# Sensors.net
KiCad netlist of a schematic drawn in Altium Designer
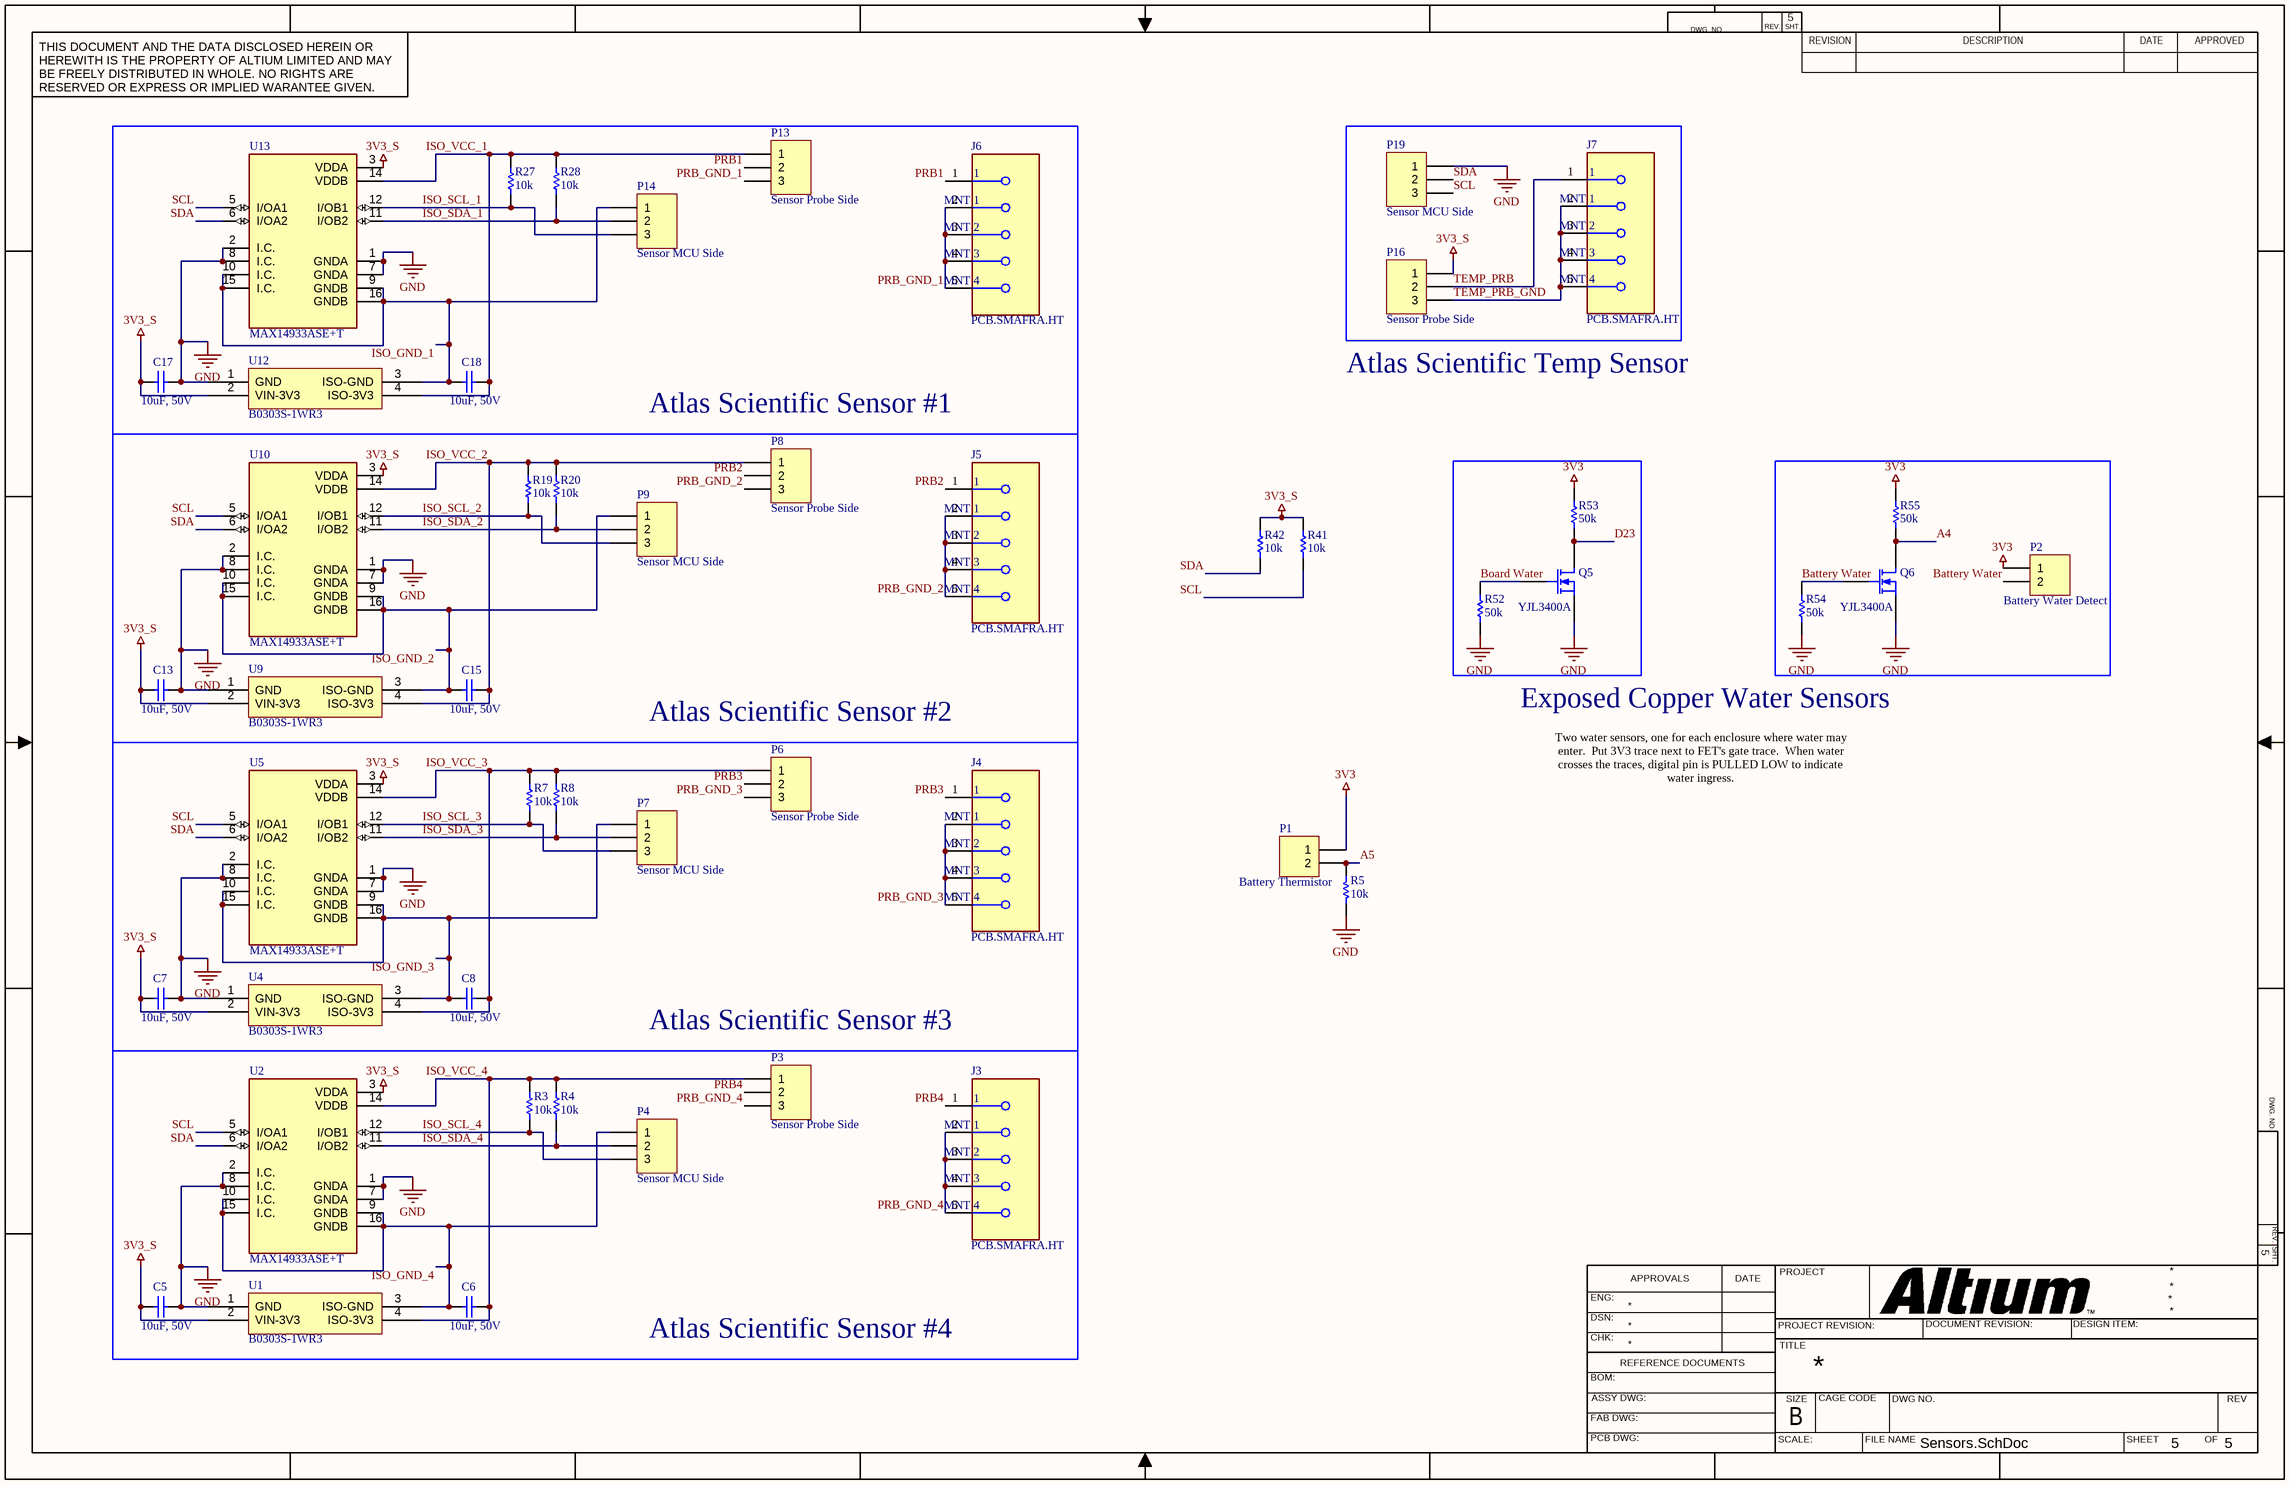
[diagram p0: Sensors.SchDoc]

(export (version "E")
  (design (tool "Eeschema 10.0.6"))
  (components
    (comp (ref "C5")
      (value "10uF, 50V")
      (footprint "CAPC2012X145N")
      (description "Capacitor")
      (libsource (lib "Simulation Generic Components") (part "Capacitor"))
    )
    (comp (ref "C6")
      (value "10uF, 50V")
      (footprint "CAPC2012X145N")
      (description "Capacitor")
      (libsource (lib "Simulation Generic Components") (part "Capacitor"))
    )
    (comp (ref "C7")
      (value "10uF, 50V")
      (footprint "CAPC2012X145N")
      (description "Capacitor")
      (libsource (lib "Simulation Generic Components") (part "Capacitor"))
    )
    (comp (ref "C8")
      (value "10uF, 50V")
      (footprint "CAPC2012X145N")
      (description "Capacitor")
      (libsource (lib "Simulation Generic Components") (part "Capacitor"))
    )
    (comp (ref "C13")
      (value "10uF, 50V")
      (footprint "CAPC2012X145N")
      (description "Capacitor")
      (libsource (lib "Simulation Generic Components") (part "Capacitor"))
    )
    (comp (ref "C15")
      (value "10uF, 50V")
      (footprint "CAPC2012X145N")
      (description "Capacitor")
      (libsource (lib "Simulation Generic Components") (part "Capacitor"))
    )
    (comp (ref "C17")
      (value "10uF, 50V")
      (footprint "CAPC2012X145N")
      (description "Capacitor")
      (libsource (lib "Simulation Generic Components") (part "Capacitor"))
    )
    (comp (ref "C18")
      (value "10uF, 50V")
      (footprint "CAPC2012X145N")
      (description "Capacitor")
      (libsource (lib "Simulation Generic Components") (part "Capacitor"))
    )
    (comp (ref "J3")
      (value "PCB.SMAFRA.HT")
      (footprint "FP-PCB_SMAFRA_HT-MFG")
      (description "CONN SMA JACK R/A 50OHM PCB")
      (libsource (lib "Altium Content Vault") (part "9c40ac4d87bbbe9fcb330bd20f98ca3"))
    )
    (comp (ref "J4")
      (value "PCB.SMAFRA.HT")
      (footprint "FP-PCB_SMAFRA_HT-MFG")
      (description "CONN SMA JACK R/A 50OHM PCB")
      (libsource (lib "Altium Content Vault") (part "9c40ac4d87bbbe9fcb330bd20f98ca3"))
    )
    (comp (ref "J5")
      (value "PCB.SMAFRA.HT")
      (footprint "FP-PCB_SMAFRA_HT-MFG")
      (description "CONN SMA JACK R/A 50OHM PCB")
      (libsource (lib "Altium Content Vault") (part "9c40ac4d87bbbe9fcb330bd20f98ca3"))
    )
    (comp (ref "J6")
      (value "PCB.SMAFRA.HT")
      (footprint "FP-PCB_SMAFRA_HT-MFG")
      (description "CONN SMA JACK R/A 50OHM PCB")
      (libsource (lib "Altium Content Vault") (part "9c40ac4d87bbbe9fcb330bd20f98ca3"))
    )
    (comp (ref "J7")
      (value "PCB.SMAFRA.HT")
      (footprint "FP-PCB_SMAFRA_HT-MFG")
      (description "CONN SMA JACK R/A 50OHM PCB")
      (libsource (lib "Altium Content Vault") (part "9c40ac4d87bbbe9fcb330bd20f98ca3"))
    )
    (comp (ref "P1")
      (value "Battery Thermistor")
      (footprint "TE_6-440054-2")
      (description "Header, 2-Pin")
      (fields (field (name "PUBLISHER") "Altium Limited"))
      (libsource (lib "") (part "Header 2_1"))
    )
    (comp (ref "P2")
      (value "Battery Water Detect")
      (footprint "TE_6-440054-2")
      (description "Header, 2-Pin")
      (fields (field (name "PUBLISHER") "Altium Limited"))
      (libsource (lib "Miscellaneous Connectors") (part "Header 2"))
    )
    (comp (ref "P3")
      (value "Sensor Probe Side")
      (footprint "1x3 Header")
      (description "Header, 3-Pin")
      (fields (field (name "PUBLISHER") "Altium Limited"))
      (libsource (lib "Miscellaneous Connectors") (part "Header 3"))
    )
    (comp (ref "P4")
      (value "Sensor MCU Side")
      (footprint "1x3 Header")
      (description "Header, 3-Pin")
      (fields (field (name "PUBLISHER") "Altium Limited"))
      (libsource (lib "Miscellaneous Connectors") (part "Header 3"))
    )
    (comp (ref "P6")
      (value "Sensor Probe Side")
      (footprint "1x3 Header")
      (description "Header, 3-Pin")
      (fields (field (name "PUBLISHER") "Altium Limited"))
      (libsource (lib "Miscellaneous Connectors") (part "Header 3"))
    )
    (comp (ref "P7")
      (value "Sensor MCU Side")
      (footprint "1x3 Header")
      (description "Header, 3-Pin")
      (fields (field (name "PUBLISHER") "Altium Limited"))
      (libsource (lib "Miscellaneous Connectors") (part "Header 3"))
    )
    (comp (ref "P8")
      (value "Sensor Probe Side")
      (footprint "1x3 Header")
      (description "Header, 3-Pin")
      (fields (field (name "PUBLISHER") "Altium Limited"))
      (libsource (lib "Miscellaneous Connectors") (part "Header 3"))
    )
    (comp (ref "P9")
      (value "Sensor MCU Side")
      (footprint "1x3 Header")
      (description "Header, 3-Pin")
      (fields (field (name "PUBLISHER") "Altium Limited"))
      (libsource (lib "Miscellaneous Connectors") (part "Header 3"))
    )
    (comp (ref "P13")
      (value "Sensor Probe Side")
      (footprint "1x3 Header")
      (description "Header, 3-Pin")
      (fields (field (name "PUBLISHER") "Altium Limited"))
      (libsource (lib "Miscellaneous Connectors") (part "Header 3"))
    )
    (comp (ref "P14")
      (value "Sensor MCU Side")
      (footprint "1x3 Header")
      (description "Header, 3-Pin")
      (fields (field (name "PUBLISHER") "Altium Limited"))
      (libsource (lib "Miscellaneous Connectors") (part "Header 3"))
    )
    (comp (ref "P16")
      (value "Sensor Probe Side")
      (footprint "1x3 Header")
      (description "Header, 3-Pin")
      (fields (field (name "PUBLISHER") "Altium Limited"))
      (libsource (lib "") (part "Header 3_2"))
    )
    (comp (ref "P19")
      (value "Sensor MCU Side")
      (footprint "1x3 Header")
      (description "Header, 3-Pin")
      (fields (field (name "PUBLISHER") "Altium Limited"))
      (libsource (lib "") (part "Header 3_1"))
    )
    (comp (ref "Q5")
      (value "YJL3400A")
      (footprint "SOT23-3")
      (description "N-Channel MOSFET")
      (fields (field (name "PUBLISHER") "Altium Limited"))
      (libsource (lib "Miscellaneous Devices") (part "MOSFET-N"))
    )
    (comp (ref "Q6")
      (value "YJL3400A")
      (footprint "SOT23-3")
      (description "N-Channel MOSFET")
      (fields (field (name "PUBLISHER") "Altium Limited"))
      (libsource (lib "Miscellaneous Devices") (part "MOSFET-N"))
    )
    (comp (ref "R3")
      (value "10k")
      (footprint "0603 Resistor")
      (description "Resistor")
      (libsource (lib "Simulation Generic Components") (part "Resistor"))
    )
    (comp (ref "R4")
      (value "10k")
      (footprint "0603 Resistor")
      (description "Resistor")
      (libsource (lib "Simulation Generic Components") (part "Resistor"))
    )
    (comp (ref "R5")
      (value "10k")
      (footprint "0603 Resistor")
      (description "Resistor")
      (libsource (lib "Simulation Generic Components") (part "Resistor"))
    )
    (comp (ref "R7")
      (value "10k")
      (footprint "0603 Resistor")
      (description "Resistor")
      (libsource (lib "Simulation Generic Components") (part "Resistor"))
    )
    (comp (ref "R8")
      (value "10k")
      (footprint "0603 Resistor")
      (description "Resistor")
      (libsource (lib "Simulation Generic Components") (part "Resistor"))
    )
    (comp (ref "R19")
      (value "10k")
      (footprint "0603 Resistor")
      (description "Resistor")
      (libsource (lib "Simulation Generic Components") (part "Resistor"))
    )
    (comp (ref "R20")
      (value "10k")
      (footprint "0603 Resistor")
      (description "Resistor")
      (libsource (lib "Simulation Generic Components") (part "Resistor"))
    )
    (comp (ref "R27")
      (value "10k")
      (footprint "0603 Resistor")
      (description "Resistor")
      (libsource (lib "Simulation Generic Components") (part "Resistor"))
    )
    (comp (ref "R28")
      (value "10k")
      (footprint "0603 Resistor")
      (description "Resistor")
      (libsource (lib "Simulation Generic Components") (part "Resistor"))
    )
    (comp (ref "R41")
      (value "10k")
      (footprint "0603 Resistor")
      (description "Resistor")
      (libsource (lib "Simulation Generic Components") (part "Resistor"))
    )
    (comp (ref "R42")
      (value "10k")
      (footprint "0603 Resistor")
      (description "Resistor")
      (libsource (lib "Simulation Generic Components") (part "Resistor"))
    )
    (comp (ref "R52")
      (value "50k")
      (footprint "0603 Resistor")
      (description "Resistor")
      (libsource (lib "Simulation Generic Components") (part "Resistor"))
    )
    (comp (ref "R53")
      (value "50k")
      (footprint "0603 Resistor")
      (description "Resistor")
      (libsource (lib "Simulation Generic Components") (part "Resistor"))
    )
    (comp (ref "R54")
      (value "50k")
      (footprint "0603 Resistor")
      (description "Resistor")
      (libsource (lib "Simulation Generic Components") (part "Resistor"))
    )
    (comp (ref "R55")
      (value "50k")
      (footprint "0603 Resistor")
      (description "Resistor")
      (libsource (lib "Simulation Generic Components") (part "Resistor"))
    )
    (comp (ref "U1")
      (value "B0303S-1WR3")
      (footprint "B0303S-1WR3")
      (description "3V3 Isolator")
      (libsource (lib "WaterNet23BotPCB") (part "B0303S-1WR3"))
    )
    (comp (ref "U2")
      (value "MAX14933ASE+T")
      (footprint "SOIC127P600X175-16N")
      (libsource (lib "MAX14933ASE+T") (part "MAX14933ASE+T"))
    )
    (comp (ref "U4")
      (value "B0303S-1WR3")
      (footprint "B0303S-1WR3")
      (description "3V3 Isolator")
      (libsource (lib "WaterNet23BotPCB") (part "B0303S-1WR3"))
    )
    (comp (ref "U5")
      (value "MAX14933ASE+T")
      (footprint "SOIC127P600X175-16N")
      (libsource (lib "MAX14933ASE+T") (part "MAX14933ASE+T"))
    )
    (comp (ref "U9")
      (value "B0303S-1WR3")
      (footprint "B0303S-1WR3")
      (description "3V3 Isolator")
      (libsource (lib "WaterNet23BotPCB") (part "B0303S-1WR3"))
    )
    (comp (ref "U10")
      (value "MAX14933ASE+T")
      (footprint "SOIC127P600X175-16N")
      (libsource (lib "MAX14933ASE+T") (part "MAX14933ASE+T"))
    )
    (comp (ref "U12")
      (value "B0303S-1WR3")
      (footprint "B0303S-1WR3")
      (description "3V3 Isolator")
      (libsource (lib "WaterNet23BotPCB") (part "B0303S-1WR3"))
    )
    (comp (ref "U13")
      (value "MAX14933ASE+T")
      (footprint "SOIC127P600X175-16N")
      (libsource (lib "MAX14933ASE+T") (part "MAX14933ASE+T"))
    )
  )
  (nets
    (net (code "1") (name "/A4") (class "Default")
      (node (ref "Q6") (pin "3") (pinfunction "D_3") (pintype "passive"))
      (node (ref "R55") (pin "1") (pinfunction "1_1") (pintype "passive"))
    )
    (net (code "2") (name "/A5") (class "Default")
      (node (ref "P1") (pin "2") (pinfunction "2_2") (pintype "passive"))
      (node (ref "R5") (pin "2") (pinfunction "2_2") (pintype "passive"))
    )
    (net (code "3") (name "/Battery Water") (class "Default")
      (node (ref "P2") (pin "2") (pinfunction "2_2") (pintype "passive"))
      (node (ref "Q6") (pin "1") (pinfunction "G_1") (pintype "passive"))
      (node (ref "R54") (pin "2") (pinfunction "2_2") (pintype "passive"))
    )
    (net (code "4") (name "/Board Water") (class "Default")
      (node (ref "Q5") (pin "1") (pinfunction "G_1") (pintype "passive"))
      (node (ref "R52") (pin "2") (pinfunction "2_2") (pintype "passive"))
    )
    (net (code "5") (name "/D23") (class "Default")
      (node (ref "Q5") (pin "3") (pinfunction "D_3") (pintype "passive"))
      (node (ref "R53") (pin "1") (pinfunction "1_1") (pintype "passive"))
    )
    (net (code "6") (name "/ISO_GND_1") (class "Default")
      (node (ref "C18") (pin "1") (pinfunction "1_1") (pintype "passive"))
      (node (ref "P14") (pin "1") (pinfunction "1_1") (pintype "passive"))
      (node (ref "U12") (pin "3") (pinfunction "ISO-GND_3") (pintype "power_in"))
      (node (ref "U13") (pin "10") (pinfunction "I.C._10") (pintype "passive"))
      (node (ref "U13") (pin "15") (pinfunction "I.C._15") (pintype "passive"))
      (node (ref "U13") (pin "16") (pinfunction "GNDB_16") (pintype "power_in"))
      (node (ref "U13") (pin "9") (pinfunction "GNDB_9") (pintype "power_in"))
    )
    (net (code "7") (name "/ISO_GND_2") (class "Default")
      (node (ref "C15") (pin "1") (pinfunction "1_1") (pintype "passive"))
      (node (ref "P9") (pin "1") (pinfunction "1_1") (pintype "passive"))
      (node (ref "U10") (pin "10") (pinfunction "I.C._10") (pintype "passive"))
      (node (ref "U10") (pin "15") (pinfunction "I.C._15") (pintype "passive"))
      (node (ref "U10") (pin "16") (pinfunction "GNDB_16") (pintype "power_in"))
      (node (ref "U10") (pin "9") (pinfunction "GNDB_9") (pintype "power_in"))
      (node (ref "U9") (pin "3") (pinfunction "ISO-GND_3") (pintype "power_in"))
    )
    (net (code "8") (name "/ISO_GND_3") (class "Default")
      (node (ref "C8") (pin "1") (pinfunction "1_1") (pintype "passive"))
      (node (ref "P7") (pin "1") (pinfunction "1_1") (pintype "passive"))
      (node (ref "U4") (pin "3") (pinfunction "ISO-GND_3") (pintype "power_in"))
      (node (ref "U5") (pin "10") (pinfunction "I.C._10") (pintype "passive"))
      (node (ref "U5") (pin "15") (pinfunction "I.C._15") (pintype "passive"))
      (node (ref "U5") (pin "16") (pinfunction "GNDB_16") (pintype "power_in"))
      (node (ref "U5") (pin "9") (pinfunction "GNDB_9") (pintype "power_in"))
    )
    (net (code "9") (name "/ISO_GND_4") (class "Default")
      (node (ref "C6") (pin "1") (pinfunction "1_1") (pintype "passive"))
      (node (ref "P4") (pin "1") (pinfunction "1_1") (pintype "passive"))
      (node (ref "U1") (pin "3") (pinfunction "ISO-GND_3") (pintype "power_in"))
      (node (ref "U2") (pin "10") (pinfunction "I.C._10") (pintype "passive"))
      (node (ref "U2") (pin "15") (pinfunction "I.C._15") (pintype "passive"))
      (node (ref "U2") (pin "16") (pinfunction "GNDB_16") (pintype "power_in"))
      (node (ref "U2") (pin "9") (pinfunction "GNDB_9") (pintype "power_in"))
    )
    (net (code "10") (name "/ISO_SCL_1") (class "Default")
      (node (ref "P14") (pin "3") (pinfunction "3_3") (pintype "passive"))
      (node (ref "R27") (pin "1") (pinfunction "1_1") (pintype "passive"))
      (node (ref "U13") (pin "12") (pinfunction "I/OB1_12") (pintype "bidirectional"))
    )
    (net (code "11") (name "/ISO_SCL_2") (class "Default")
      (node (ref "P9") (pin "3") (pinfunction "3_3") (pintype "passive"))
      (node (ref "R19") (pin "1") (pinfunction "1_1") (pintype "passive"))
      (node (ref "U10") (pin "12") (pinfunction "I/OB1_12") (pintype "bidirectional"))
    )
    (net (code "12") (name "/ISO_SCL_3") (class "Default")
      (node (ref "P7") (pin "3") (pinfunction "3_3") (pintype "passive"))
      (node (ref "R7") (pin "1") (pinfunction "1_1") (pintype "passive"))
      (node (ref "U5") (pin "12") (pinfunction "I/OB1_12") (pintype "bidirectional"))
    )
    (net (code "13") (name "/ISO_SCL_4") (class "Default")
      (node (ref "P4") (pin "3") (pinfunction "3_3") (pintype "passive"))
      (node (ref "R3") (pin "1") (pinfunction "1_1") (pintype "passive"))
      (node (ref "U2") (pin "12") (pinfunction "I/OB1_12") (pintype "bidirectional"))
    )
    (net (code "14") (name "/ISO_SDA_1") (class "Default")
      (node (ref "P14") (pin "2") (pinfunction "2_2") (pintype "passive"))
      (node (ref "R28") (pin "1") (pinfunction "1_1") (pintype "passive"))
      (node (ref "U13") (pin "11") (pinfunction "I/OB2_11") (pintype "bidirectional"))
    )
    (net (code "15") (name "/ISO_SDA_2") (class "Default")
      (node (ref "P9") (pin "2") (pinfunction "2_2") (pintype "passive"))
      (node (ref "R20") (pin "1") (pinfunction "1_1") (pintype "passive"))
      (node (ref "U10") (pin "11") (pinfunction "I/OB2_11") (pintype "bidirectional"))
    )
    (net (code "16") (name "/ISO_SDA_3") (class "Default")
      (node (ref "P7") (pin "2") (pinfunction "2_2") (pintype "passive"))
      (node (ref "R8") (pin "1") (pinfunction "1_1") (pintype "passive"))
      (node (ref "U5") (pin "11") (pinfunction "I/OB2_11") (pintype "bidirectional"))
    )
    (net (code "17") (name "/ISO_SDA_4") (class "Default")
      (node (ref "P4") (pin "2") (pinfunction "2_2") (pintype "passive"))
      (node (ref "R4") (pin "1") (pinfunction "1_1") (pintype "passive"))
      (node (ref "U2") (pin "11") (pinfunction "I/OB2_11") (pintype "bidirectional"))
    )
    (net (code "18") (name "/ISO_VCC_1") (class "Default")
      (node (ref "C18") (pin "2") (pinfunction "2_2") (pintype "passive"))
      (node (ref "P13") (pin "1") (pinfunction "1_1") (pintype "passive"))
      (node (ref "R27") (pin "2") (pinfunction "2_2") (pintype "passive"))
      (node (ref "R28") (pin "2") (pinfunction "2_2") (pintype "passive"))
      (node (ref "U12") (pin "4") (pinfunction "ISO-3V3_4") (pintype "power_in"))
      (node (ref "U13") (pin "14") (pinfunction "VDDB_14") (pintype "power_in"))
    )
    (net (code "19") (name "/ISO_VCC_2") (class "Default")
      (node (ref "C15") (pin "2") (pinfunction "2_2") (pintype "passive"))
      (node (ref "P8") (pin "1") (pinfunction "1_1") (pintype "passive"))
      (node (ref "R19") (pin "2") (pinfunction "2_2") (pintype "passive"))
      (node (ref "R20") (pin "2") (pinfunction "2_2") (pintype "passive"))
      (node (ref "U10") (pin "14") (pinfunction "VDDB_14") (pintype "power_in"))
      (node (ref "U9") (pin "4") (pinfunction "ISO-3V3_4") (pintype "power_in"))
    )
    (net (code "20") (name "/ISO_VCC_3") (class "Default")
      (node (ref "C8") (pin "2") (pinfunction "2_2") (pintype "passive"))
      (node (ref "P6") (pin "1") (pinfunction "1_1") (pintype "passive"))
      (node (ref "R7") (pin "2") (pinfunction "2_2") (pintype "passive"))
      (node (ref "R8") (pin "2") (pinfunction "2_2") (pintype "passive"))
      (node (ref "U4") (pin "4") (pinfunction "ISO-3V3_4") (pintype "power_in"))
      (node (ref "U5") (pin "14") (pinfunction "VDDB_14") (pintype "power_in"))
    )
    (net (code "21") (name "/ISO_VCC_4") (class "Default")
      (node (ref "C6") (pin "2") (pinfunction "2_2") (pintype "passive"))
      (node (ref "P3") (pin "1") (pinfunction "1_1") (pintype "passive"))
      (node (ref "R3") (pin "2") (pinfunction "2_2") (pintype "passive"))
      (node (ref "R4") (pin "2") (pinfunction "2_2") (pintype "passive"))
      (node (ref "U1") (pin "4") (pinfunction "ISO-3V3_4") (pintype "power_in"))
      (node (ref "U2") (pin "14") (pinfunction "VDDB_14") (pintype "power_in"))
    )
    (net (code "22") (name "/PRB1") (class "Default")
      (node (ref "J6") (pin "1") (pinfunction "1_1") (pintype "passive"))
      (node (ref "P13") (pin "2") (pinfunction "2_2") (pintype "passive"))
    )
    (net (code "23") (name "/PRB2") (class "Default")
      (node (ref "J5") (pin "1") (pinfunction "1_1") (pintype "passive"))
      (node (ref "P8") (pin "2") (pinfunction "2_2") (pintype "passive"))
    )
    (net (code "24") (name "/PRB3") (class "Default")
      (node (ref "J4") (pin "1") (pinfunction "1_1") (pintype "passive"))
      (node (ref "P6") (pin "2") (pinfunction "2_2") (pintype "passive"))
    )
    (net (code "25") (name "/PRB4") (class "Default")
      (node (ref "J3") (pin "1") (pinfunction "1_1") (pintype "passive"))
      (node (ref "P3") (pin "2") (pinfunction "2_2") (pintype "passive"))
    )
    (net (code "26") (name "/PRB_GND_1") (class "Default")
      (node (ref "J6") (pin "2") (pinfunction "MNT_1_2") (pintype "passive"))
      (node (ref "J6") (pin "3") (pinfunction "MNT_2_3") (pintype "passive"))
      (node (ref "J6") (pin "4") (pinfunction "MNT_3_4") (pintype "passive"))
      (node (ref "J6") (pin "5") (pinfunction "MNT_4_5") (pintype "passive"))
      (node (ref "P13") (pin "3") (pinfunction "3_3") (pintype "passive"))
    )
    (net (code "27") (name "/PRB_GND_2") (class "Default")
      (node (ref "J5") (pin "2") (pinfunction "MNT_1_2") (pintype "passive"))
      (node (ref "J5") (pin "3") (pinfunction "MNT_2_3") (pintype "passive"))
      (node (ref "J5") (pin "4") (pinfunction "MNT_3_4") (pintype "passive"))
      (node (ref "J5") (pin "5") (pinfunction "MNT_4_5") (pintype "passive"))
      (node (ref "P8") (pin "3") (pinfunction "3_3") (pintype "passive"))
    )
    (net (code "28") (name "/PRB_GND_3") (class "Default")
      (node (ref "J4") (pin "2") (pinfunction "MNT_1_2") (pintype "passive"))
      (node (ref "J4") (pin "3") (pinfunction "MNT_2_3") (pintype "passive"))
      (node (ref "J4") (pin "4") (pinfunction "MNT_3_4") (pintype "passive"))
      (node (ref "J4") (pin "5") (pinfunction "MNT_4_5") (pintype "passive"))
      (node (ref "P6") (pin "3") (pinfunction "3_3") (pintype "passive"))
    )
    (net (code "29") (name "/PRB_GND_4") (class "Default")
      (node (ref "J3") (pin "2") (pinfunction "MNT_1_2") (pintype "passive"))
      (node (ref "J3") (pin "3") (pinfunction "MNT_2_3") (pintype "passive"))
      (node (ref "J3") (pin "4") (pinfunction "MNT_3_4") (pintype "passive"))
      (node (ref "J3") (pin "5") (pinfunction "MNT_4_5") (pintype "passive"))
      (node (ref "P3") (pin "3") (pinfunction "3_3") (pintype "passive"))
    )
    (net (code "30") (name "/SCL") (class "Default")
      (node (ref "P19") (pin "3") (pinfunction "3_3") (pintype "passive"))
      (node (ref "R41") (pin "1") (pinfunction "1_1") (pintype "passive"))
      (node (ref "U10") (pin "5") (pinfunction "I/OA1_5") (pintype "bidirectional"))
      (node (ref "U13") (pin "5") (pinfunction "I/OA1_5") (pintype "bidirectional"))
      (node (ref "U2") (pin "5") (pinfunction "I/OA1_5") (pintype "bidirectional"))
      (node (ref "U5") (pin "5") (pinfunction "I/OA1_5") (pintype "bidirectional"))
    )
    (net (code "31") (name "/SDA") (class "Default")
      (node (ref "P19") (pin "2") (pinfunction "2_2") (pintype "passive"))
      (node (ref "R42") (pin "1") (pinfunction "1_1") (pintype "passive"))
      (node (ref "U10") (pin "6") (pinfunction "I/OA2_6") (pintype "bidirectional"))
      (node (ref "U13") (pin "6") (pinfunction "I/OA2_6") (pintype "bidirectional"))
      (node (ref "U2") (pin "6") (pinfunction "I/OA2_6") (pintype "bidirectional"))
      (node (ref "U5") (pin "6") (pinfunction "I/OA2_6") (pintype "bidirectional"))
    )
    (net (code "32") (name "/TEMP_PRB") (class "Default")
      (node (ref "J7") (pin "1") (pinfunction "1_1") (pintype "passive"))
      (node (ref "P16") (pin "2") (pinfunction "2_2") (pintype "power_in"))
    )
    (net (code "33") (name "/TEMP_PRB_GND") (class "Default")
      (node (ref "J7") (pin "2") (pinfunction "MNT_1_2") (pintype "passive"))
      (node (ref "J7") (pin "3") (pinfunction "MNT_2_3") (pintype "passive"))
      (node (ref "J7") (pin "4") (pinfunction "MNT_3_4") (pintype "passive"))
      (node (ref "J7") (pin "5") (pinfunction "MNT_4_5") (pintype "passive"))
      (node (ref "P16") (pin "3") (pinfunction "3_3") (pintype "power_in"))
    )
    (net (code "34") (name "3V3") (class "Default")
      (node (ref "P1") (pin "1") (pinfunction "1_1") (pintype "passive"))
      (node (ref "P2") (pin "1") (pinfunction "1_1") (pintype "passive"))
      (node (ref "R53") (pin "2") (pinfunction "2_2") (pintype "passive"))
      (node (ref "R55") (pin "2") (pinfunction "2_2") (pintype "passive"))
    )
    (net (code "35") (name "3V3_S") (class "Default")
      (node (ref "C13") (pin "1") (pinfunction "1_1") (pintype "passive"))
      (node (ref "C17") (pin "1") (pinfunction "1_1") (pintype "passive"))
      (node (ref "C5") (pin "1") (pinfunction "1_1") (pintype "passive"))
      (node (ref "C7") (pin "1") (pinfunction "1_1") (pintype "passive"))
      (node (ref "P16") (pin "1") (pinfunction "1_1") (pintype "power_in"))
      (node (ref "R41") (pin "2") (pinfunction "2_2") (pintype "passive"))
      (node (ref "R42") (pin "2") (pinfunction "2_2") (pintype "passive"))
      (node (ref "U1") (pin "2") (pinfunction "VIN-3V3_2") (pintype "power_in"))
      (node (ref "U10") (pin "3") (pinfunction "VDDA_3") (pintype "power_in"))
      (node (ref "U12") (pin "2") (pinfunction "VIN-3V3_2") (pintype "power_in"))
      (node (ref "U13") (pin "3") (pinfunction "VDDA_3") (pintype "power_in"))
      (node (ref "U2") (pin "3") (pinfunction "VDDA_3") (pintype "power_in"))
      (node (ref "U4") (pin "2") (pinfunction "VIN-3V3_2") (pintype "power_in"))
      (node (ref "U5") (pin "3") (pinfunction "VDDA_3") (pintype "power_in"))
      (node (ref "U9") (pin "2") (pinfunction "VIN-3V3_2") (pintype "power_in"))
    )
    (net (code "36") (name "GND") (class "Default")
      (node (ref "C13") (pin "2") (pinfunction "2_2") (pintype "passive"))
      (node (ref "C17") (pin "2") (pinfunction "2_2") (pintype "passive"))
      (node (ref "C5") (pin "2") (pinfunction "2_2") (pintype "passive"))
      (node (ref "C7") (pin "2") (pinfunction "2_2") (pintype "passive"))
      (node (ref "P19") (pin "1") (pinfunction "1_1") (pintype "passive"))
      (node (ref "Q5") (pin "2") (pinfunction "S_2") (pintype "passive"))
      (node (ref "Q6") (pin "2") (pinfunction "S_2") (pintype "passive"))
      (node (ref "R5") (pin "1") (pinfunction "1_1") (pintype "passive"))
      (node (ref "R52") (pin "1") (pinfunction "1_1") (pintype "passive"))
      (node (ref "R54") (pin "1") (pinfunction "1_1") (pintype "passive"))
      (node (ref "U1") (pin "1") (pinfunction "GND_1") (pintype "power_in"))
      (node (ref "U10") (pin "1") (pinfunction "GNDA_1") (pintype "power_in"))
      (node (ref "U10") (pin "2") (pinfunction "I.C._2") (pintype "passive"))
      (node (ref "U10") (pin "7") (pinfunction "GNDA_7") (pintype "power_in"))
      (node (ref "U10") (pin "8") (pinfunction "I.C._8") (pintype "passive"))
      (node (ref "U12") (pin "1") (pinfunction "GND_1") (pintype "power_in"))
      (node (ref "U13") (pin "1") (pinfunction "GNDA_1") (pintype "power_in"))
      (node (ref "U13") (pin "2") (pinfunction "I.C._2") (pintype "passive"))
      (node (ref "U13") (pin "7") (pinfunction "GNDA_7") (pintype "power_in"))
      (node (ref "U13") (pin "8") (pinfunction "I.C._8") (pintype "passive"))
      (node (ref "U2") (pin "1") (pinfunction "GNDA_1") (pintype "power_in"))
      (node (ref "U2") (pin "2") (pinfunction "I.C._2") (pintype "passive"))
      (node (ref "U2") (pin "7") (pinfunction "GNDA_7") (pintype "power_in"))
      (node (ref "U2") (pin "8") (pinfunction "I.C._8") (pintype "passive"))
      (node (ref "U4") (pin "1") (pinfunction "GND_1") (pintype "power_in"))
      (node (ref "U5") (pin "1") (pinfunction "GNDA_1") (pintype "power_in"))
      (node (ref "U5") (pin "2") (pinfunction "I.C._2") (pintype "passive"))
      (node (ref "U5") (pin "7") (pinfunction "GNDA_7") (pintype "power_in"))
      (node (ref "U5") (pin "8") (pinfunction "I.C._8") (pintype "passive"))
      (node (ref "U9") (pin "1") (pinfunction "GND_1") (pintype "power_in"))
    )
  )
)
